# PADS_Project.net
KiCad netlist of a schematic drawn in Altium Designer
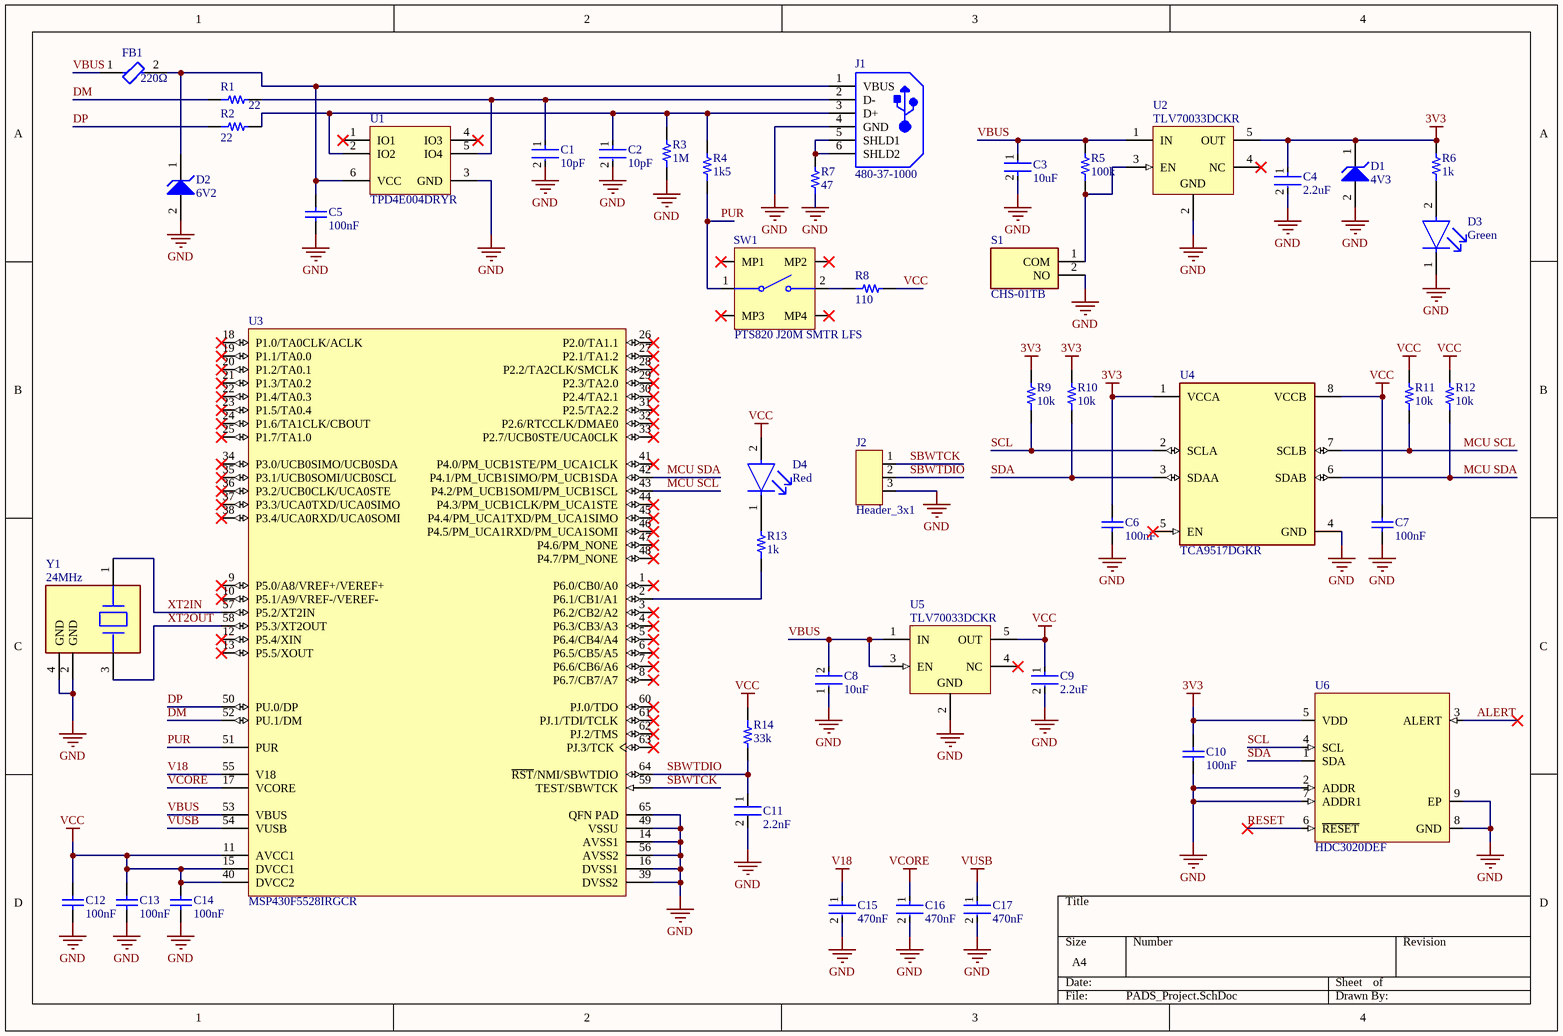
[diagram p0: PADS_Project.SchDoc]

(export (version "E")
  (design (tool "Eeschema 10.0.6"))
  (components
    (comp (ref "C1")
      (value "10pF")
      (footprint "FP-C0402-BB-IPC_A")
      (description "C0402C100K4GACTU\r\nCAP CER 10PF 16V 10% NP0 0402")
      (fields
        (field (name "MANUFACTURER PART NUMBER") "C0402C100K4GACTU")
        (field (name "MANUFACTURER") "Kemet")
      )
      (libsource (lib "Altium Content Vault") (part "b4654b650e69147ec39a6b967a45e02"))
    )
    (comp (ref "C2")
      (value "10pF")
      (footprint "FP-C0402-BB-IPC_A")
      (description "C0402C100K4GACTU\r\nCAP CER 10PF 16V 10% NP0 0402")
      (fields
        (field (name "MANUFACTURER PART NUMBER") "C0402C100K4GACTU")
        (field (name "MANUFACTURER") "Kemet")
      )
      (libsource (lib "Altium Content Vault") (part "b4654b650e69147ec39a6b967a45e02"))
    )
    (comp (ref "C3")
      (value "10uF")
      (footprint "FP-C1608-080-0_1-IPC_A")
      (description "C1608X5R1A106M080AC\r\nMultilayer Ceramic Capacitors 10μF ±20% 10V X5R SMD 0603")
      (fields (field (name "TOLERANCE") "20%"))
      (libsource (lib "Altium Content Vault") (part "236180d848d6139a670b325ea6854c9"))
    )
    (comp (ref "C4")
      (value "2.2uF")
      (footprint "FP-GRM155-0_2-IPC_A")
      (fields (field (name "TOLERANCE") "10%"))
      (libsource (lib "Altium Content Vault") (part "b4654b650e69147ec39a6b967a45e02"))
    )
    (comp (ref "C5")
      (value "100nF")
      (footprint "CAPC1005X55X25LL05T10")
      (description "LMK105BJ104KV-F\r\nCAP, CERM, 0.1 uF, 10\r\nV,+/- 10%, X5R, 0402")
      (fields (field (name "TOLERANCE") "10%"))
      (libsource (lib "Altium Content Vault") (part "CAP-NP-2"))
    )
    (comp (ref "C6")
      (value "100nF")
      (footprint "CAPC1005X55X25ML05T10")
      (description "LMK105BJ104KV-F\r\nCAP, CERM, 0.1 uF, 10\r\nV,+/- 10%, X5R, 0402")
      (fields (field (name "TOLERANCE") "10%"))
      (libsource (lib "Altium Content Vault") (part "CAP-NP-2"))
    )
    (comp (ref "C7")
      (value "100nF")
      (footprint "CAPC1005X55X25ML05T10")
      (description "LMK105BJ104KV-F\r\nCAP, CERM, 0.1 uF, 10\r\nV,+/- 10%, X5R, 0402")
      (fields (field (name "TOLERANCE") "10%"))
      (libsource (lib "Altium Content Vault") (part "CAP-NP-2"))
    )
    (comp (ref "C8")
      (value "10uF")
      (footprint "FP-C1608-080-0_1-IPC_A")
      (description "C1608X5R1A106M080AC\r\nMultilayer Ceramic Capacitors 10μF ±20% 10V X5R SMD 0603")
      (fields (field (name "TOLERANCE") "20%"))
      (libsource (lib "Altium Content Vault") (part "236180d848d6139a670b325ea6854c9"))
    )
    (comp (ref "C9")
      (value "2.2uF")
      (footprint "FP-GRM155-0_2-IPC_A")
      (fields (field (name "TOLERANCE") "10%"))
      (libsource (lib "Altium Content Vault") (part "b4654b650e69147ec39a6b967a45e02"))
    )
    (comp (ref "C10")
      (value "100nF")
      (footprint "CAPC1005X55X25ML05T10")
      (description "LMK105BJ104KV-F\r\nCAP, CERM, 0.1 uF, 10\r\nV,+/- 10%, X5R, 0402")
      (fields (field (name "TOLERANCE") "10%"))
      (libsource (lib "Altium Content Vault") (part "CAP-NP-2"))
    )
    (comp (ref "C11")
      (value "2.2nF")
      (footprint "RES")
      (description "CL05B222JB5NNNC\r\nCAP, CERM, 2200 pF, 50\r\nV, +/- 5%, X7R, 0402")
      (libsource (lib "PADS_SchLib") (part "CAP"))
    )
    (comp (ref "C12")
      (value "100nF")
      (footprint "CAPC1005X55X25ML05T10")
      (description "LMK105BJ104KV-F\r\nCAP, CERM, 0.1 uF, 10\r\nV,+/- 10%, X5R, 0402")
      (fields (field (name "TOLERANCE") "10%"))
      (libsource (lib "Altium Content Vault") (part "CAP-NP-2"))
    )
    (comp (ref "C13")
      (value "100nF")
      (footprint "CAPC1005X55X25ML05T10")
      (description "LMK105BJ104KV-F\r\nCAP, CERM, 0.1 uF, 10\r\nV,+/- 10%, X5R, 0402")
      (fields (field (name "TOLERANCE") "10%"))
      (libsource (lib "Altium Content Vault") (part "CAP-NP-2"))
    )
    (comp (ref "C14")
      (value "100nF")
      (footprint "CAPC1005X55X25ML05T10")
      (description "LMK105BJ104KV-F\r\nCAP, CERM, 0.1 uF, 10\r\nV,+/- 10%, X5R, 0402")
      (fields (field (name "TOLERANCE") "10%"))
      (libsource (lib "Altium Content Vault") (part "CAP-NP-2"))
    )
    (comp (ref "C15")
      (value "470nF")
      (footprint "FP-0402-L_1_0_0_05-W_0_5-IPC_A")
      (description "JMK105B7474KVHF\r\nCAP, CERM, 0.47 uF, 6.3\r\nV, +/- 10%, X7R, 0402")
      (fields (field (name "TOLERANCE") "10%"))
      (libsource (lib "Altium Content Vault") (part "b4654b650e69147ec39a6b967a45e02"))
    )
    (comp (ref "C16")
      (value "470nF")
      (footprint "FP-0402-L_1_0_0_05-W_0_5-IPC_A")
      (description "JMK105B7474KVHF\r\nCAP, CERM, 0.47 uF, 6.3\r\nV, +/- 10%, X7R, 0402")
      (fields (field (name "TOLERANCE") "10%"))
      (libsource (lib "Altium Content Vault") (part "b4654b650e69147ec39a6b967a45e02"))
    )
    (comp (ref "C17")
      (value "470nF")
      (footprint "FP-0402-L_1_0_0_05-W_0_5-IPC_A")
      (description "JMK105B7474KVHF\r\nCAP, CERM, 0.47 uF, 6.3\r\nV, +/- 10%, X7R, 0402")
      (fields (field (name "TOLERANCE") "10%"))
      (libsource (lib "Altium Content Vault") (part "b4654b650e69147ec39a6b967a45e02"))
    )
    (comp (ref "D1")
      (value "4V3")
      (footprint "ONSC-SOD-323-2-477-02_V")
      (description "SZMM3Z4V3T1G\r\nZener Voltage Regulator, 300 mW, 2-Pin SOD-323, Pb-Free, Tape and Reel")
      (fields (field (name "PARTNUMBER") "SZMM3Z4V3T1G") (field (name "MANUFACTURER") "On Semiconductor"))
      (libsource (lib "Altium Content Vault") (part "ONSC-K1A2-2"))
    )
    (comp (ref "D2")
      (value "6V2")
      (footprint "ONSC-SOD-323-2-477-02_V")
      (fields (field (name "PARTNUMBER") "SZMM3Z6V2ST1G") (field (name "MANUFACTURER") "On Semiconductor"))
      (libsource (lib "Altium Content Vault") (part "ONSC-K1A2-2"))
    )
    (comp (ref "D3")
      (value "Green")
      (footprint "FP-APHCM2012CGCK-F01-MFG")
      (description "APHCM2012CGCK-F01\r\nLED GREEN CLEAR CHIP SMD")
      (libsource (lib "Altium Content Vault") (part "8706943c75ba83719d021d2fdc84c58"))
    )
    (comp (ref "D4")
      (value "Red")
      (footprint "FP-SML-LX0603SIW-TR-MFG")
      (description "SML-LX0603SIW-TR\r\nLED RED DIFFUSED SMD")
      (libsource (lib "Altium Content Vault") (part "8706943c75ba83719d021d2fdc84c58"))
    )
    (comp (ref "FB1")
      (value "220Ω")
      (footprint "FP-BLM15-0_05-IPC_A")
      (description "Chip Ferrite Bead, 0402, 220Ω @ 100MHz, 0.29Ω, 25%, 450mA")
      (fields (field (name "TOLERANCE") "25%"))
      (libsource (lib "Altium Content Vault") (part "5f30dd21d616792df468990f7003faa"))
    )
    (comp (ref "J1")
      (value "480-37-1000")
      (footprint "MOLX-480-37-1000_V")
      (fields (field (name "TOLERANCE") "1%"))
      (libsource (lib "Altium Content Vault") (part "USB-4-2SHLD"))
    )
    (comp (ref "J2")
      (value "Header_3x1")
      (footprint "Header_3x1")
      (libsource (lib "PADS_SchLib") (part "Header 3x1"))
    )
    (comp (ref "R1") (value "22") (footprint "RES") (libsource (lib "PADS_SchLib") (part "RES")))
    (comp (ref "R2") (value "22") (footprint "RES") (libsource (lib "PADS_SchLib") (part "RES")))
    (comp (ref "R3") (value "1M") (footprint "RES") (libsource (lib "PADS_SchLib") (part "RES")))
    (comp (ref "R4") (value "1k5") (footprint "RES") (libsource (lib "PADS_SchLib") (part "RES")))
    (comp (ref "R5") (value "100k") (footprint "RES") (libsource (lib "PADS_SchLib") (part "RES")))
    (comp (ref "R6") (value "1k") (footprint "RES") (libsource (lib "PADS_SchLib") (part "RES")))
    (comp (ref "R7") (value "47") (footprint "RES") (libsource (lib "PADS_SchLib") (part "RES")))
    (comp (ref "R8") (value "110") (footprint "RES") (libsource (lib "PADS_SchLib") (part "RES")))
    (comp (ref "R9") (value "10k") (footprint "RES") (libsource (lib "PADS_SchLib") (part "RES")))
    (comp (ref "R10") (value "10k") (footprint "RES") (libsource (lib "PADS_SchLib") (part "RES")))
    (comp (ref "R11") (value "10k") (footprint "RES") (libsource (lib "PADS_SchLib") (part "RES")))
    (comp (ref "R12") (value "10k") (footprint "RES") (libsource (lib "PADS_SchLib") (part "RES")))
    (comp (ref "R13") (value "1k") (footprint "RES") (libsource (lib "PADS_SchLib") (part "RES")))
    (comp (ref "R14") (value "33k") (footprint "RES") (libsource (lib "PADS_SchLib") (part "RES")))
    (comp (ref "S1")
      (value "CHS-01TB")
      (footprint "CHS01TB")
      (description "DIP Switches / SIP Switches smd slide 1 pos., gull wing, washable with seal tape, 1/2 pitch")
      (fields (field (name "MOUSER PART NUMBER") "229-CHS-01TB"))
      (libsource (lib "PADS_SchLib") (part "CHS-01TB"))
    )
    (comp (ref "SW1")
      (value "PTS820 J20M SMTR LFS")
      (footprint "PTS820J20MPSMTRLFS")
      (libsource (lib "PADS_SchLib") (part "PTS820 J20M SMTR LFS"))
    )
    (comp (ref "U1")
      (value "TPD4E004DRYR")
      (footprint "DRY0006A")
      (fields (field (name "MANUFACTURER") "Texas Instruments"))
      (libsource (lib "Altium Content Vault") (part "TI-TPD4E004-SON_DRY-6"))
    )
    (comp (ref "U2")
      (value "TLV70033DCKR")
      (footprint "DCK0005A_M")
      (fields (field (name "MANUFACTURER") "Texas Instruments"))
      (libsource (lib "Altium Content Vault") (part "TI-TXX7XXXX-5"))
    )
    (comp (ref "U3")
      (value "MSP430F5528IRGCR")
      (footprint "RGC0064B")
      (fields (field (name "MANUFACTURER") "Texas Instruments"))
      (libsource (lib "Altium Content Vault") (part "TI-MSP430F5528-RGC64"))
    )
    (comp (ref "U4")
      (value "TCA9517DGKR")
      (footprint "FP-DGK0008A-MFG")
      (description "IC TRNSLTR BIDIRECTIONAL 8VSSOP")
      (fields
        (field (name "OCTOPART") "https://octopart.com/tca9517dgkr-texas+instruments-25896020")
        (field (name "MANUFACTURER") "Texas Instruments")
      )
      (libsource (lib "Altium Content Vault") (part "4650ad196f2c887cce9edf5941dd529"))
    )
    (comp (ref "U5")
      (value "TLV70033DCKR")
      (footprint "DCK0005A_M")
      (fields (field (name "MANUFACTURER") "Texas Instruments"))
      (libsource (lib "Altium Content Vault") (part "TI-TXX7XXXX-5"))
    )
    (comp (ref "U6")
      (value "HDC3020DEF")
      (footprint "SON50P250X250X80-9N-D")
      (libsource (lib "PADS_SchLib") (part "HDC3020DEF"))
    )
    (comp (ref "Y1")
      (value "24MHz")
      (footprint "FP-ABM11W-MFG")
      (description "ABM11W-24.0000MHZ-8-K1Z-T3\r\nCrystal 24MHz ±10ppm 8pF SMD-4 2mm x 1.6mm")
      (libsource (lib "Altium Content Vault") (part "5fba445d8d5f95165d6b3865099b029"))
    )
  )
  (nets
    (net (code "1") (name "/ALERT") (class "Default")
      (node (ref "U6") (pin "3") (pinfunction "ALERT_3") (pintype "input+no_connect"))
    )
    (net (code "2") (name "/DM") (class "Default")
      (node (ref "R1") (pin "1") (pintype "passive"))
      (node (ref "U3") (pin "52") (pinfunction "PU.1/DM_52") (pintype "bidirectional"))
    )
    (net (code "3") (name "/DP") (class "Default")
      (node (ref "R2") (pin "1") (pintype "passive"))
      (node (ref "U3") (pin "50") (pinfunction "PU.0/DP_50") (pintype "bidirectional"))
    )
    (net (code "4") (name "/MCU SCL") (class "Default")
      (node (ref "R11") (pin "1") (pintype "passive"))
      (node (ref "U3") (pin "43") (pinfunction "P4.2/PM_UCB1SOMI/PM_UCB1SCL_43") (pintype "bidirectional"))
      (node (ref "U4") (pin "7") (pinfunction "SCLB_7") (pintype "bidirectional"))
    )
    (net (code "5") (name "/MCU SDA") (class "Default")
      (node (ref "R12") (pin "1") (pintype "passive"))
      (node (ref "U3") (pin "42") (pinfunction "P4.1/PM_UCB1SIMO/PM_UCB1SDA_42") (pintype "bidirectional"))
      (node (ref "U4") (pin "6") (pinfunction "SDAB_6") (pintype "bidirectional"))
    )
    (net (code "6") (name "/PUR") (class "Default")
      (node (ref "R4") (pin "1") (pintype "passive"))
      (node (ref "SW1") (pin "1") (pintype "passive"))
      (node (ref "U3") (pin "51") (pinfunction "PUR_51") (pintype "passive"))
    )
    (net (code "7") (name "/RESET") (class "Default")
      (node (ref "U6") (pin "6") (pinfunction "~{RESET}_6") (pintype "input+no_connect"))
    )
    (net (code "8") (name "/SBWTCK") (class "Default")
      (node (ref "J2") (pin "1") (pintype "passive"))
      (node (ref "U3") (pin "59") (pinfunction "TEST/SBWTCK_59") (pintype "input"))
    )
    (net (code "9") (name "/SBWTDIO") (class "Default")
      (node (ref "C11") (pin "1") (pintype "passive"))
      (node (ref "J2") (pin "2") (pintype "passive"))
      (node (ref "R14") (pin "2") (pintype "passive"))
      (node (ref "U3") (pin "64") (pinfunction "~{RST}/NMI/SBWTDIO_64") (pintype "bidirectional"))
    )
    (net (code "10") (name "/SCL") (class "Default")
      (node (ref "R9") (pin "1") (pintype "passive"))
      (node (ref "U4") (pin "2") (pinfunction "SCLA_2") (pintype "bidirectional"))
      (node (ref "U6") (pin "4") (pinfunction "SCL_4") (pintype "input"))
    )
    (net (code "11") (name "/SDA") (class "Default")
      (node (ref "R10") (pin "1") (pintype "passive"))
      (node (ref "U4") (pin "3") (pinfunction "SDAA_3") (pintype "bidirectional"))
      (node (ref "U6") (pin "1") (pinfunction "SDA_1") (pintype "bidirectional"))
    )
    (net (code "12") (name "/VBUS") (class "Default")
      (node (ref "C3") (pin "1") (pinfunction "1_1") (pintype "passive"))
      (node (ref "C8") (pin "2") (pinfunction "2_2") (pintype "passive"))
      (node (ref "FB1") (pin "1") (pinfunction "1_1") (pintype "passive"))
      (node (ref "R5") (pin "2") (pintype "passive"))
      (node (ref "U2") (pin "1") (pinfunction "IN_1") (pintype "power_in"))
      (node (ref "U3") (pin "53") (pinfunction "VBUS_53") (pintype "power_in"))
      (node (ref "U5") (pin "1") (pinfunction "IN_1") (pintype "power_in"))
      (node (ref "U5") (pin "3") (pinfunction "EN_3") (pintype "input"))
    )
    (net (code "13") (name "/XT2IN") (class "Default")
      (node (ref "U3") (pin "57") (pinfunction "P5.2/XT2IN_57") (pintype "bidirectional"))
      (node (ref "Y1") (pin "1") (pinfunction "1_1") (pintype "passive"))
    )
    (net (code "14") (name "/XT2OUT") (class "Default")
      (node (ref "U3") (pin "58") (pinfunction "P5.3/XT2OUT_58") (pintype "bidirectional"))
      (node (ref "Y1") (pin "3") (pinfunction "3_3") (pintype "passive"))
    )
    (net (code "15") (name "3V3") (class "Default")
      (node (ref "C10") (pin "2") (pinfunction "2_2") (pintype "passive"))
      (node (ref "C4") (pin "1") (pinfunction "1_1") (pintype "passive"))
      (node (ref "C6") (pin "2") (pinfunction "2_2") (pintype "passive"))
      (node (ref "D1") (pin "1") (pinfunction "K_1") (pintype "passive"))
      (node (ref "R10") (pin "2") (pintype "passive"))
      (node (ref "R6") (pin "2") (pintype "passive"))
      (node (ref "R9") (pin "2") (pintype "passive"))
      (node (ref "U2") (pin "5") (pinfunction "OUT_5") (pintype "power_in"))
      (node (ref "U4") (pin "1") (pinfunction "VCCA_1") (pintype "power_in"))
      (node (ref "U6") (pin "5") (pinfunction "VDD_5") (pintype "passive"))
    )
    (net (code "16") (name "GND") (class "Default")
      (node (ref "C1") (pin "2") (pinfunction "2_2") (pintype "passive"))
      (node (ref "C10") (pin "1") (pinfunction "1_1") (pintype "passive"))
      (node (ref "C11") (pin "2") (pintype "passive"))
      (node (ref "C12") (pin "1") (pinfunction "1_1") (pintype "passive"))
      (node (ref "C13") (pin "1") (pinfunction "1_1") (pintype "passive"))
      (node (ref "C14") (pin "1") (pinfunction "1_1") (pintype "passive"))
      (node (ref "C15") (pin "2") (pinfunction "2_2") (pintype "passive"))
      (node (ref "C16") (pin "2") (pinfunction "2_2") (pintype "passive"))
      (node (ref "C17") (pin "2") (pinfunction "2_2") (pintype "passive"))
      (node (ref "C2") (pin "2") (pinfunction "2_2") (pintype "passive"))
      (node (ref "C3") (pin "2") (pinfunction "2_2") (pintype "passive"))
      (node (ref "C4") (pin "2") (pinfunction "2_2") (pintype "passive"))
      (node (ref "C5") (pin "1") (pinfunction "1_1") (pintype "passive"))
      (node (ref "C6") (pin "1") (pinfunction "1_1") (pintype "passive"))
      (node (ref "C7") (pin "1") (pinfunction "1_1") (pintype "passive"))
      (node (ref "C8") (pin "1") (pinfunction "1_1") (pintype "passive"))
      (node (ref "C9") (pin "2") (pinfunction "2_2") (pintype "passive"))
      (node (ref "D1") (pin "2") (pinfunction "A_2") (pintype "passive"))
      (node (ref "D2") (pin "2") (pinfunction "A_2") (pintype "passive"))
      (node (ref "D3") (pin "1") (pinfunction "C_1") (pintype "passive"))
      (node (ref "J1") (pin "4") (pinfunction "GND_4") (pintype "passive"))
      (node (ref "J2") (pin "3") (pintype "passive"))
      (node (ref "R3") (pin "1") (pintype "passive"))
      (node (ref "R7") (pin "1") (pintype "passive"))
      (node (ref "S1") (pin "2") (pinfunction "NO_2") (pintype "passive"))
      (node (ref "U1") (pin "3") (pinfunction "GND_3") (pintype "power_in"))
      (node (ref "U2") (pin "2") (pinfunction "GND_2") (pintype "power_in"))
      (node (ref "U3") (pin "14") (pinfunction "AVSS1_14") (pintype "power_in"))
      (node (ref "U3") (pin "16") (pinfunction "DVSS1_16") (pintype "power_in"))
      (node (ref "U3") (pin "39") (pinfunction "DVSS2_39") (pintype "power_in"))
      (node (ref "U3") (pin "49") (pinfunction "VSSU_49") (pintype "power_in"))
      (node (ref "U3") (pin "56") (pinfunction "AVSS2_56") (pintype "power_in"))
      (node (ref "U3") (pin "65") (pinfunction "QFN_PAD_65") (pintype "power_in"))
      (node (ref "U4") (pin "4") (pinfunction "GND_4") (pintype "power_in"))
      (node (ref "U5") (pin "2") (pinfunction "GND_2") (pintype "power_in"))
      (node (ref "U6") (pin "2") (pinfunction "ADDR_2") (pintype "input"))
      (node (ref "U6") (pin "7") (pinfunction "ADDR1_7") (pintype "input"))
      (node (ref "U6") (pin "8") (pinfunction "GND_8") (pintype "passive"))
      (node (ref "U6") (pin "9") (pinfunction "EP_9") (pintype "passive"))
      (node (ref "Y1") (pin "2") (pinfunction "GND_2") (pintype "power_in"))
      (node (ref "Y1") (pin "4") (pinfunction "GND_4") (pintype "power_in"))
    )
    (net (code "17") (name "Net-(D2-K)") (class "Default")
      (node (ref "C5") (pin "2") (pinfunction "2_2") (pintype "passive"))
      (node (ref "D2") (pin "1") (pinfunction "K_1") (pintype "passive"))
      (node (ref "FB1") (pin "2") (pinfunction "2_2") (pintype "passive"))
      (node (ref "J1") (pin "1") (pinfunction "VBUS_1") (pintype "passive"))
      (node (ref "U1") (pin "6") (pinfunction "VCC_6") (pintype "power_in"))
    )
    (net (code "18") (name "Net-(D3-A)") (class "Default")
      (node (ref "D3") (pin "2") (pinfunction "A_2") (pintype "passive"))
      (node (ref "R6") (pin "1") (pintype "passive"))
    )
    (net (code "19") (name "Net-(D4-C)") (class "Default")
      (node (ref "D4") (pin "1") (pinfunction "C_1") (pintype "passive"))
      (node (ref "R13") (pin "2") (pintype "passive"))
    )
    (net (code "20") (name "Net-(J1-D+)") (class "Default")
      (node (ref "C2") (pin "1") (pinfunction "1_1") (pintype "passive"))
      (node (ref "J1") (pin "3") (pinfunction "D+_3") (pintype "passive"))
      (node (ref "R2") (pin "2") (pintype "passive"))
      (node (ref "R3") (pin "2") (pintype "passive"))
      (node (ref "R4") (pin "2") (pintype "passive"))
      (node (ref "U1") (pin "2") (pinfunction "IO2_2") (pintype "passive"))
    )
    (net (code "21") (name "Net-(J1-D-)") (class "Default")
      (node (ref "C1") (pin "1") (pinfunction "1_1") (pintype "passive"))
      (node (ref "J1") (pin "2") (pinfunction "D-_2") (pintype "passive"))
      (node (ref "R1") (pin "2") (pintype "passive"))
      (node (ref "U1") (pin "5") (pinfunction "IO4_5") (pintype "passive"))
    )
    (net (code "22") (name "Net-(J1-SHLD1)") (class "Default")
      (node (ref "J1") (pin "5") (pinfunction "SHLD1_5") (pintype "passive"))
      (node (ref "J1") (pin "6") (pinfunction "SHLD2_6") (pintype "passive"))
      (node (ref "R7") (pin "2") (pintype "passive"))
    )
    (net (code "23") (name "Net-(R8-Pad1)") (class "Default")
      (node (ref "R8") (pin "1") (pintype "passive"))
      (node (ref "SW1") (pin "2") (pintype "passive"))
    )
    (net (code "24") (name "Net-(S1-COM)") (class "Default")
      (node (ref "R5") (pin "1") (pintype "passive"))
      (node (ref "S1") (pin "1") (pinfunction "COM_1") (pintype "passive"))
      (node (ref "U2") (pin "3") (pinfunction "EN_3") (pintype "input"))
    )
    (net (code "25") (name "Net-(U3-P6.1{slash}CB1{slash}A1)") (class "Default")
      (node (ref "R13") (pin "1") (pintype "passive"))
      (node (ref "U3") (pin "2") (pinfunction "P6.1/CB1/A1_2") (pintype "bidirectional"))
    )
    (net (code "26") (name "V18") (class "Default")
      (node (ref "C15") (pin "1") (pinfunction "1_1") (pintype "passive"))
      (node (ref "U3") (pin "55") (pinfunction "V18_55") (pintype "passive"))
    )
    (net (code "27") (name "VCC") (class "Default")
      (node (ref "C12") (pin "2") (pinfunction "2_2") (pintype "passive"))
      (node (ref "C13") (pin "2") (pinfunction "2_2") (pintype "passive"))
      (node (ref "C14") (pin "2") (pinfunction "2_2") (pintype "passive"))
      (node (ref "C7") (pin "2") (pinfunction "2_2") (pintype "passive"))
      (node (ref "C9") (pin "1") (pinfunction "1_1") (pintype "passive"))
      (node (ref "D4") (pin "2") (pinfunction "A_2") (pintype "passive"))
      (node (ref "R11") (pin "2") (pintype "passive"))
      (node (ref "R12") (pin "2") (pintype "passive"))
      (node (ref "R14") (pin "1") (pintype "passive"))
      (node (ref "R8") (pin "2") (pintype "passive"))
      (node (ref "U3") (pin "11") (pinfunction "AVCC1_11") (pintype "power_in"))
      (node (ref "U3") (pin "15") (pinfunction "DVCC1_15") (pintype "power_in"))
      (node (ref "U3") (pin "40") (pinfunction "DVCC2_40") (pintype "power_in"))
      (node (ref "U4") (pin "8") (pinfunction "VCCB_8") (pintype "power_in"))
      (node (ref "U5") (pin "5") (pinfunction "OUT_5") (pintype "power_in"))
    )
    (net (code "28") (name "VCORE") (class "Default")
      (node (ref "C16") (pin "1") (pinfunction "1_1") (pintype "passive"))
      (node (ref "U3") (pin "17") (pinfunction "VCORE_17") (pintype "passive"))
    )
    (net (code "29") (name "VUSB") (class "Default")
      (node (ref "C17") (pin "1") (pinfunction "1_1") (pintype "passive"))
      (node (ref "U3") (pin "54") (pinfunction "VUSB_54") (pintype "power_in"))
    )
    (net (code "30") (name "unconnected-(SW1-MP1-Pad)") (class "Default")
      (node (ref "SW1") (pin "") (pinfunction "MP1_") (pintype "passive+no_connect"))
    )
    (net (code "31") (name "unconnected-(SW1-MP2-Pad)") (class "Default")
      (node (ref "SW1") (pin "") (pinfunction "MP2_") (pintype "passive+no_connect"))
    )
    (net (code "32") (name "unconnected-(SW1-MP3-Pad)") (class "Default")
      (node (ref "SW1") (pin "") (pinfunction "MP3_") (pintype "passive+no_connect"))
    )
    (net (code "33") (name "unconnected-(SW1-MP4-Pad)") (class "Default")
      (node (ref "SW1") (pin "") (pinfunction "MP4_") (pintype "passive+no_connect"))
    )
    (net (code "34") (name "unconnected-(U1-IO1-Pad1)") (class "Default")
      (node (ref "U1") (pin "1") (pinfunction "IO1_1") (pintype "passive+no_connect"))
    )
    (net (code "35") (name "unconnected-(U1-IO3-Pad4)") (class "Default")
      (node (ref "U1") (pin "4") (pinfunction "IO3_4") (pintype "passive+no_connect"))
    )
    (net (code "36") (name "unconnected-(U2-NC-Pad4)") (class "Default")
      (node (ref "U2") (pin "4") (pinfunction "NC_4") (pintype "passive+no_connect"))
    )
    (net (code "37") (name "unconnected-(U3-P1.0{slash}TA0CLK{slash}ACLK-Pad18)") (class "Default")
      (node (ref "U3") (pin "18") (pinfunction "P1.0/TA0CLK/ACLK_18") (pintype "bidirectional+no_connect"))
    )
    (net (code "38") (name "unconnected-(U3-P1.1{slash}TA0.0-Pad19)") (class "Default")
      (node (ref "U3") (pin "19") (pinfunction "P1.1/TA0.0_19") (pintype "bidirectional+no_connect"))
    )
    (net (code "39") (name "unconnected-(U3-P1.2{slash}TA0.1-Pad20)") (class "Default")
      (node (ref "U3") (pin "20") (pinfunction "P1.2/TA0.1_20") (pintype "bidirectional+no_connect"))
    )
    (net (code "40") (name "unconnected-(U3-P1.3{slash}TA0.2-Pad21)") (class "Default")
      (node (ref "U3") (pin "21") (pinfunction "P1.3/TA0.2_21") (pintype "bidirectional+no_connect"))
    )
    (net (code "41") (name "unconnected-(U3-P1.4{slash}TA0.3-Pad22)") (class "Default")
      (node (ref "U3") (pin "22") (pinfunction "P1.4/TA0.3_22") (pintype "bidirectional+no_connect"))
    )
    (net (code "42") (name "unconnected-(U3-P1.5{slash}TA0.4-Pad23)") (class "Default")
      (node (ref "U3") (pin "23") (pinfunction "P1.5/TA0.4_23") (pintype "bidirectional+no_connect"))
    )
    (net (code "43") (name "unconnected-(U3-P1.6{slash}TA1CLK{slash}CBOUT-Pad24)") (class "Default")
      (node (ref "U3") (pin "24") (pinfunction "P1.6/TA1CLK/CBOUT_24") (pintype "bidirectional+no_connect"))
    )
    (net (code "44") (name "unconnected-(U3-P1.7{slash}TA1.0-Pad25)") (class "Default")
      (node (ref "U3") (pin "25") (pinfunction "P1.7/TA1.0_25") (pintype "bidirectional+no_connect"))
    )
    (net (code "45") (name "unconnected-(U3-P2.0{slash}TA1.1-Pad26)") (class "Default")
      (node (ref "U3") (pin "26") (pinfunction "P2.0/TA1.1_26") (pintype "bidirectional+no_connect"))
    )
    (net (code "46") (name "unconnected-(U3-P2.1{slash}TA1.2-Pad27)") (class "Default")
      (node (ref "U3") (pin "27") (pinfunction "P2.1/TA1.2_27") (pintype "bidirectional+no_connect"))
    )
    (net (code "47") (name "unconnected-(U3-P2.2{slash}TA2CLK{slash}SMCLK-Pad28)") (class "Default")
      (node (ref "U3") (pin "28") (pinfunction "P2.2/TA2CLK/SMCLK_28") (pintype "bidirectional+no_connect"))
    )
    (net (code "48") (name "unconnected-(U3-P2.3{slash}TA2.0-Pad29)") (class "Default")
      (node (ref "U3") (pin "29") (pinfunction "P2.3/TA2.0_29") (pintype "bidirectional+no_connect"))
    )
    (net (code "49") (name "unconnected-(U3-P2.4{slash}TA2.1-Pad30)") (class "Default")
      (node (ref "U3") (pin "30") (pinfunction "P2.4/TA2.1_30") (pintype "bidirectional+no_connect"))
    )
    (net (code "50") (name "unconnected-(U3-P2.5{slash}TA2.2-Pad31)") (class "Default")
      (node (ref "U3") (pin "31") (pinfunction "P2.5/TA2.2_31") (pintype "bidirectional+no_connect"))
    )
    (net (code "51") (name "unconnected-(U3-P2.6{slash}RTCCLK{slash}DMAE0-Pad32)") (class "Default")
      (node (ref "U3") (pin "32") (pinfunction "P2.6/RTCCLK/DMAE0_32") (pintype "bidirectional+no_connect"))
    )
    (net (code "52") (name "unconnected-(U3-P2.7{slash}UCB0STE{slash}UCA0CLK-Pad33)") (class "Default")
      (node (ref "U3") (pin "33") (pinfunction "P2.7/UCB0STE/UCA0CLK_33") (pintype "bidirectional+no_connect"))
    )
    (net (code "53") (name "unconnected-(U3-P3.0{slash}UCB0SIMO{slash}UCB0SDA-Pad34)") (class "Default")
      (node (ref "U3") (pin "34") (pinfunction "P3.0/UCB0SIMO/UCB0SDA_34") (pintype "bidirectional+no_connect"))
    )
    (net (code "54") (name "unconnected-(U3-P3.1{slash}UCB0SOMI{slash}UCB0SCL-Pad35)") (class "Default")
      (node (ref "U3") (pin "35") (pinfunction "P3.1/UCB0SOMI/UCB0SCL_35") (pintype "bidirectional+no_connect"))
    )
    (net (code "55") (name "unconnected-(U3-P3.2{slash}UCB0CLK{slash}UCA0STE-Pad36)") (class "Default")
      (node (ref "U3") (pin "36") (pinfunction "P3.2/UCB0CLK/UCA0STE_36") (pintype "bidirectional+no_connect"))
    )
    (net (code "56") (name "unconnected-(U3-P3.3{slash}UCA0TXD{slash}UCA0SIMO-Pad37)") (class "Default")
      (node (ref "U3") (pin "37") (pinfunction "P3.3/UCA0TXD/UCA0SIMO_37") (pintype "bidirectional+no_connect"))
    )
    (net (code "57") (name "unconnected-(U3-P3.4{slash}UCA0RXD{slash}UCA0SOMI-Pad38)") (class "Default")
      (node (ref "U3") (pin "38") (pinfunction "P3.4/UCA0RXD/UCA0SOMI_38") (pintype "bidirectional+no_connect"))
    )
    (net (code "58") (name "unconnected-(U3-P4.0{slash}PM_UCB1STE{slash}PM_UCA1CLK-Pad41)") (class "Default")
      (node (ref "U3") (pin "41") (pinfunction "P4.0/PM_UCB1STE/PM_UCA1CLK_41") (pintype "bidirectional+no_connect"))
    )
    (net (code "59") (name "unconnected-(U3-P4.3{slash}PM_UCB1CLK{slash}PM_UCA1STE-Pad44)") (class "Default")
      (node (ref "U3") (pin "44") (pinfunction "P4.3/PM_UCB1CLK/PM_UCA1STE_44") (pintype "bidirectional+no_connect"))
    )
    (net (code "60") (name "unconnected-(U3-P4.4{slash}PM_UCA1TXD{slash}PM_UCA1SIMO-Pad45)") (class "Default")
      (node (ref "U3") (pin "45") (pinfunction "P4.4/PM_UCA1TXD/PM_UCA1SIMO_45") (pintype "bidirectional+no_connect"))
    )
    (net (code "61") (name "unconnected-(U3-P4.5{slash}PM_UCA1RXD{slash}PM_UCA1SOMI-Pad46)") (class "Default")
      (node (ref "U3") (pin "46") (pinfunction "P4.5/PM_UCA1RXD/PM_UCA1SOMI_46") (pintype "bidirectional+no_connect"))
    )
    (net (code "62") (name "unconnected-(U3-P4.6{slash}PM_NONE-Pad47)") (class "Default")
      (node (ref "U3") (pin "47") (pinfunction "P4.6/PM_NONE_47") (pintype "bidirectional+no_connect"))
    )
    (net (code "63") (name "unconnected-(U3-P4.7{slash}PM_NONE-Pad48)") (class "Default")
      (node (ref "U3") (pin "48") (pinfunction "P4.7/PM_NONE_48") (pintype "bidirectional+no_connect"))
    )
    (net (code "64") (name "unconnected-(U3-P5.0{slash}A8{slash}VREF+{slash}VEREF+-Pad9)") (class "Default")
      (node (ref "U3") (pin "9") (pinfunction "P5.0/A8/VREF+/VEREF+_9") (pintype "bidirectional+no_connect"))
    )
    (net (code "65") (name "unconnected-(U3-P5.1{slash}A9{slash}VREF-{slash}VEREF--Pad10)") (class "Default")
      (node (ref "U3") (pin "10") (pinfunction "P5.1/A9/VREF-/VEREF-_10") (pintype "bidirectional+no_connect"))
    )
    (net (code "66") (name "unconnected-(U3-P5.4{slash}XIN-Pad12)") (class "Default")
      (node (ref "U3") (pin "12") (pinfunction "P5.4/XIN_12") (pintype "bidirectional+no_connect"))
    )
    (net (code "67") (name "unconnected-(U3-P5.5{slash}XOUT-Pad13)") (class "Default")
      (node (ref "U3") (pin "13") (pinfunction "P5.5/XOUT_13") (pintype "bidirectional+no_connect"))
    )
    (net (code "68") (name "unconnected-(U3-P6.0{slash}CB0{slash}A0-Pad1)") (class "Default")
      (node (ref "U3") (pin "1") (pinfunction "P6.0/CB0/A0_1") (pintype "bidirectional+no_connect"))
    )
    (net (code "69") (name "unconnected-(U3-P6.2{slash}CB2{slash}A2-Pad3)") (class "Default")
      (node (ref "U3") (pin "3") (pinfunction "P6.2/CB2/A2_3") (pintype "bidirectional+no_connect"))
    )
    (net (code "70") (name "unconnected-(U3-P6.3{slash}CB3{slash}A3-Pad4)") (class "Default")
      (node (ref "U3") (pin "4") (pinfunction "P6.3/CB3/A3_4") (pintype "bidirectional+no_connect"))
    )
    (net (code "71") (name "unconnected-(U3-P6.4{slash}CB4{slash}A4-Pad5)") (class "Default")
      (node (ref "U3") (pin "5") (pinfunction "P6.4/CB4/A4_5") (pintype "bidirectional+no_connect"))
    )
    (net (code "72") (name "unconnected-(U3-P6.5{slash}CB5{slash}A5-Pad6)") (class "Default")
      (node (ref "U3") (pin "6") (pinfunction "P6.5/CB5/A5_6") (pintype "bidirectional+no_connect"))
    )
    (net (code "73") (name "unconnected-(U3-P6.6{slash}CB6{slash}A6-Pad7)") (class "Default")
      (node (ref "U3") (pin "7") (pinfunction "P6.6/CB6/A6_7") (pintype "bidirectional+no_connect"))
    )
    (net (code "74") (name "unconnected-(U3-P6.7{slash}CB7{slash}A7-Pad8)") (class "Default")
      (node (ref "U3") (pin "8") (pinfunction "P6.7/CB7/A7_8") (pintype "bidirectional+no_connect"))
    )
    (net (code "75") (name "unconnected-(U3-PJ.0{slash}TDO-Pad60)") (class "Default")
      (node (ref "U3") (pin "60") (pinfunction "PJ.0/TDO_60") (pintype "bidirectional+no_connect"))
    )
    (net (code "76") (name "unconnected-(U3-PJ.1{slash}TDI{slash}TCLK-Pad61)") (class "Default")
      (node (ref "U3") (pin "61") (pinfunction "PJ.1/TDI/TCLK_61") (pintype "bidirectional+no_connect"))
    )
    (net (code "77") (name "unconnected-(U3-PJ.2{slash}TMS-Pad62)") (class "Default")
      (node (ref "U3") (pin "62") (pinfunction "PJ.2/TMS_62") (pintype "bidirectional+no_connect"))
    )
    (net (code "78") (name "unconnected-(U3-PJ.3{slash}TCK-Pad63)") (class "Default")
      (node (ref "U3") (pin "63") (pinfunction "PJ.3/TCK_63") (pintype "bidirectional+no_connect"))
    )
    (net (code "79") (name "unconnected-(U4-EN-Pad5)") (class "Default")
      (node (ref "U4") (pin "5") (pinfunction "EN_5") (pintype "input+no_connect"))
    )
    (net (code "80") (name "unconnected-(U5-NC-Pad4)") (class "Default")
      (node (ref "U5") (pin "4") (pinfunction "NC_4") (pintype "passive+no_connect"))
    )
  )
)
